# xmas-snow_sob.net
KiCad netlist of a schematic drawn in EAGLE
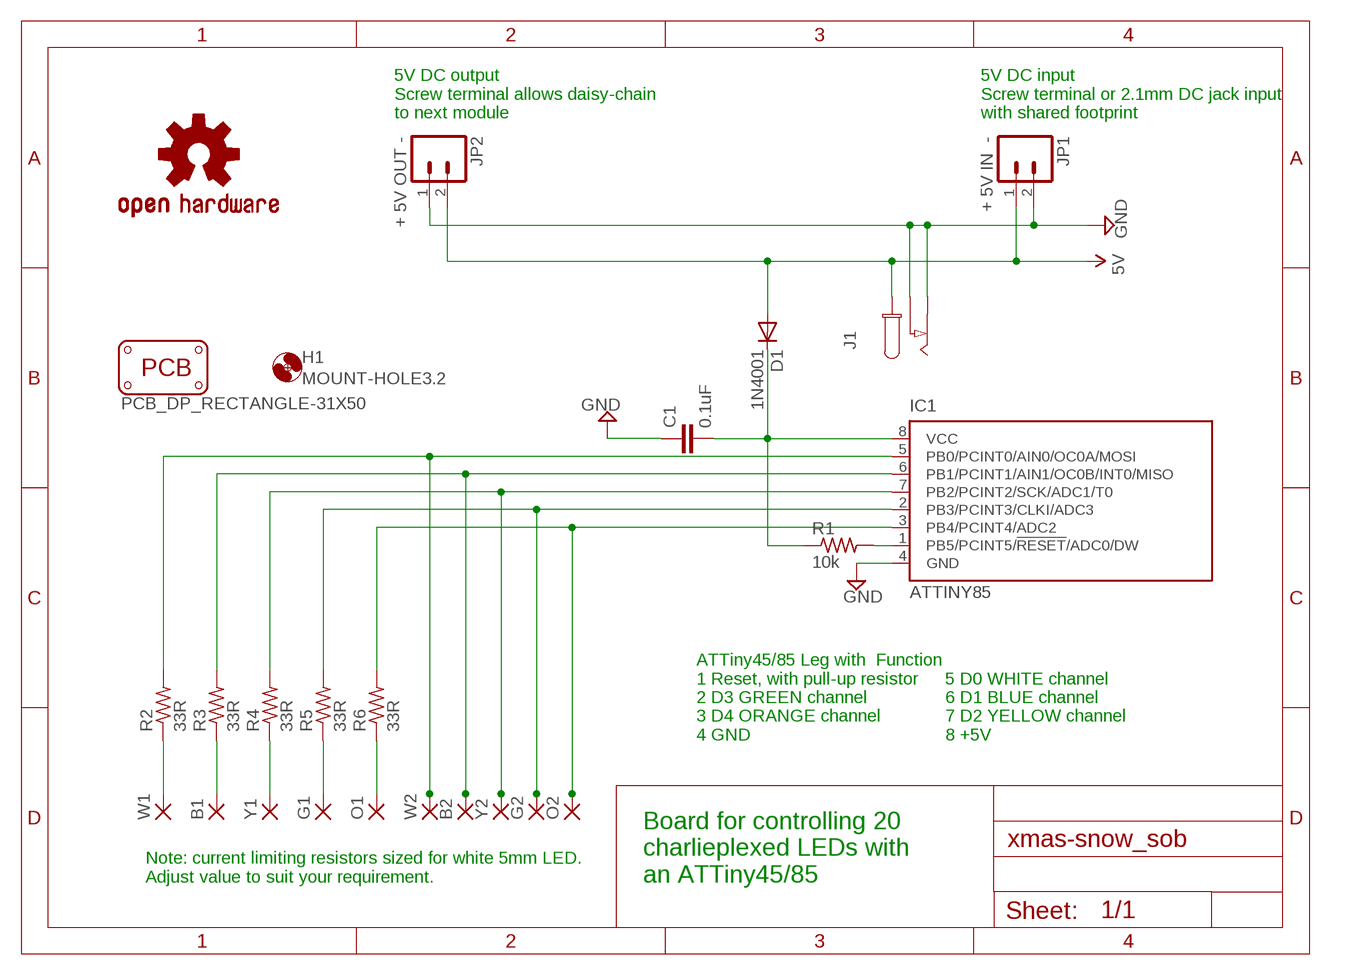
[diagram p0: schematic, sheet 1]

(export (version "E")
  (design (tool "Eeschema 10.0.6"))
  (components
    (comp (ref "B1")
      (value "WIREPAD1,6/0,8")
      (footprint "eagle-import:1,6_0,8")
      (libsource (lib "eagle-import") (part "WIREPAD1,6/0,8"))
    )
    (comp (ref "B2")
      (value "WIREPAD1,6/0,8")
      (footprint "eagle-import:1,6_0,8")
      (libsource (lib "eagle-import") (part "WIREPAD1,6/0,8"))
    )
    (comp (ref "C1")
      (value "0.1uF")
      (footprint "eagle-import:CAP-PTH-SMALL2")
      (libsource (lib "eagle-import") (part "CAPPTH2"))
    )
    (comp (ref "D1")
      (value "1N4001")
      (footprint "eagle-import:DO41-10")
      (libsource (lib "eagle-import") (part "1N4004"))
    )
    (comp (ref "G1")
      (value "WIREPAD1,6/0,8")
      (footprint "eagle-import:1,6_0,8")
      (libsource (lib "eagle-import") (part "WIREPAD1,6/0,8"))
    )
    (comp (ref "G2")
      (value "WIREPAD1,6/0,8")
      (footprint "eagle-import:1,6_0,8")
      (libsource (lib "eagle-import") (part "WIREPAD1,6/0,8"))
    )
    (comp (ref "H1")
      (value "MOUNT-HOLE3.2")
      (footprint "eagle-import:3,2")
      (libsource (lib "eagle-import") (part "MOUNT-HOLE3.2"))
    )
    (comp (ref "IC1")
      (value "ATTINY85")
      (footprint "eagle-import:DIL08")
      (fields (field (name "MPN") "ATTINY13-20PU"))
      (libsource (lib "eagle-import") (part "TINY13PU-20"))
    )
    (comp (ref "J1")
      (value "CON_DC_M-DC_PTH")
      (footprint "eagle-import:DC_BARREL_JACK_PTH_2MM")
      (libsource (lib "eagle-import") (part "CON_DC_M-DC_PTH"))
    )
    (comp (ref "JP1")
      (value "+ 5V IN -")
      (footprint "eagle-import:SCREWTERMINAL-5MM-2")
      (libsource (lib "eagle-import") (part "M025MM"))
    )
    (comp (ref "JP2")
      (value "+ 5V OUT -")
      (footprint "eagle-import:SCREWTERMINAL-5MM-2")
      (libsource (lib "eagle-import") (part "M025MM"))
    )
    (comp (ref "LOGO1")
      (value "OSHW-LOGOL")
      (footprint "eagle-import:OSHW-LOGO-L")
      (libsource (lib "eagle-import") (part "OSHW-LOGOL"))
    )
    (comp (ref "O1")
      (value "WIREPAD1,6/0,8")
      (footprint "eagle-import:1,6_0,8")
      (libsource (lib "eagle-import") (part "WIREPAD1,6/0,8"))
    )
    (comp (ref "O2")
      (value "WIREPAD1,6/0,8")
      (footprint "eagle-import:1,6_0,8")
      (libsource (lib "eagle-import") (part "WIREPAD1,6/0,8"))
    )
    (comp (ref "PCB1")
      (value "PCB_DP_RECTANGLE-31X50")
      (footprint "eagle-import:DP5031_V1")
      (libsource (lib "eagle-import") (part "PCB_DP_RECTANGLE-31X50"))
    )
    (comp (ref "R1")
      (value "10k")
      (footprint "eagle-import:0207_2V")
      (libsource (lib "eagle-import") (part "R-US_0207/2V"))
    )
    (comp (ref "R2")
      (value "33R")
      (footprint "eagle-import:0207_2V")
      (libsource (lib "eagle-import") (part "R-US_0207/2V"))
    )
    (comp (ref "R3")
      (value "33R")
      (footprint "eagle-import:0207_2V")
      (libsource (lib "eagle-import") (part "R-US_0207/2V"))
    )
    (comp (ref "R4")
      (value "33R")
      (footprint "eagle-import:0207_2V")
      (libsource (lib "eagle-import") (part "R-US_0207/2V"))
    )
    (comp (ref "R5")
      (value "33R")
      (footprint "eagle-import:0207_2V")
      (libsource (lib "eagle-import") (part "R-US_0207/2V"))
    )
    (comp (ref "R6")
      (value "33R")
      (footprint "eagle-import:0207_2V")
      (libsource (lib "eagle-import") (part "R-US_0207/2V"))
    )
    (comp (ref "W1")
      (value "WIREPAD1,6/0,8")
      (footprint "eagle-import:1,6_0,8")
      (libsource (lib "eagle-import") (part "WIREPAD1,6/0,8"))
    )
    (comp (ref "W2")
      (value "WIREPAD1,6/0,8")
      (footprint "eagle-import:1,6_0,8")
      (libsource (lib "eagle-import") (part "WIREPAD1,6/0,8"))
    )
    (comp (ref "Y1")
      (value "WIREPAD1,6/0,8")
      (footprint "eagle-import:1,6_0,8")
      (libsource (lib "eagle-import") (part "WIREPAD1,6/0,8"))
    )
    (comp (ref "Y2")
      (value "WIREPAD1,6/0,8")
      (footprint "eagle-import:1,6_0,8")
      (libsource (lib "eagle-import") (part "WIREPAD1,6/0,8"))
    )
  )
  (nets
    (net (code "1") (name "5V") (class "Default")
      (node (ref "C1") (pin "2") (pinfunction "2_2") (pintype "passive"))
      (node (ref "D1") (pin "A") (pinfunction "A_A") (pintype "passive"))
      (node (ref "D1") (pin "C") (pinfunction "C_C") (pintype "passive"))
      (node (ref "IC1") (pin "8") (pinfunction "VCC_8") (pintype "power_in"))
      (node (ref "J1") (pin "P1") (pinfunction "P1_P1") (pintype "passive"))
      (node (ref "JP1") (pin "1") (pinfunction "1_1") (pintype "passive"))
      (node (ref "JP2") (pin "2") (pinfunction "2_2") (pintype "passive"))
      (node (ref "R1") (pin "1") (pinfunction "1_1") (pintype "passive"))
    )
    (net (code "2") (name "GND") (class "Default")
      (node (ref "C1") (pin "1") (pinfunction "1_1") (pintype "passive"))
      (node (ref "IC1") (pin "4") (pinfunction "GND_4") (pintype "power_in"))
      (node (ref "J1") (pin "P2") (pinfunction "P3_P2") (pintype "passive"))
      (node (ref "J1") (pin "P3") (pinfunction "P2_P3") (pintype "passive"))
      (node (ref "JP1") (pin "2") (pinfunction "2_2") (pintype "passive"))
      (node (ref "JP2") (pin "1") (pinfunction "1_1") (pintype "passive"))
    )
    (net (code "3") (name "Net-(B1-P)") (class "Default")
      (node (ref "B1") (pin "1") (pinfunction "P_1") (pintype "passive"))
      (node (ref "R3") (pin "1") (pinfunction "1_1") (pintype "passive"))
    )
    (net (code "4") (name "Net-(B2-P)") (class "Default")
      (node (ref "B2") (pin "1") (pinfunction "P_1") (pintype "passive"))
      (node (ref "IC1") (pin "6") (pinfunction "PB1/PCINT1/AIN1/OC0B/INT0/MISO_6") (pintype "bidirectional"))
      (node (ref "R3") (pin "2") (pinfunction "2_2") (pintype "passive"))
    )
    (net (code "5") (name "Net-(G1-P)") (class "Default")
      (node (ref "G1") (pin "1") (pinfunction "P_1") (pintype "passive"))
      (node (ref "R5") (pin "1") (pinfunction "1_1") (pintype "passive"))
    )
    (net (code "6") (name "Net-(G2-P)") (class "Default")
      (node (ref "G2") (pin "1") (pinfunction "P_1") (pintype "passive"))
      (node (ref "IC1") (pin "2") (pinfunction "PB3/PCINT3/CLKI/ADC3_2") (pintype "bidirectional"))
      (node (ref "R5") (pin "2") (pinfunction "2_2") (pintype "passive"))
    )
    (net (code "7") (name "Net-(IC1-PB0{slash}PCINT0{slash}AIN0{slash}OC0A{slash}MOSI)") (class "Default")
      (node (ref "IC1") (pin "5") (pinfunction "PB0/PCINT0/AIN0/OC0A/MOSI_5") (pintype "bidirectional"))
      (node (ref "R2") (pin "2") (pinfunction "2_2") (pintype "passive"))
      (node (ref "W2") (pin "1") (pinfunction "P_1") (pintype "passive"))
    )
    (net (code "8") (name "Net-(IC1-PB2{slash}PCINT2{slash}SCK{slash}ADC1{slash}T0)") (class "Default")
      (node (ref "IC1") (pin "7") (pinfunction "PB2/PCINT2/SCK/ADC1/T0_7") (pintype "bidirectional"))
      (node (ref "R4") (pin "2") (pinfunction "2_2") (pintype "passive"))
      (node (ref "Y2") (pin "1") (pinfunction "P_1") (pintype "passive"))
    )
    (net (code "9") (name "Net-(IC1-PB4{slash}PCINT4{slash}ADC2)") (class "Default")
      (node (ref "IC1") (pin "3") (pinfunction "PB4/PCINT4/ADC2_3") (pintype "bidirectional"))
      (node (ref "O2") (pin "1") (pinfunction "P_1") (pintype "passive"))
      (node (ref "R6") (pin "2") (pinfunction "2_2") (pintype "passive"))
    )
    (net (code "10") (name "Net-(IC1-PB5{slash}PCINT5{slash}~{RESET}{slash}ADC0{slash}DW)") (class "Default")
      (node (ref "IC1") (pin "1") (pinfunction "PB5/PCINT5/~{RESET}/ADC0/DW_1") (pintype "bidirectional"))
      (node (ref "R1") (pin "2") (pinfunction "2_2") (pintype "passive"))
    )
    (net (code "11") (name "Net-(O1-P)") (class "Default")
      (node (ref "O1") (pin "1") (pinfunction "P_1") (pintype "passive"))
      (node (ref "R6") (pin "1") (pinfunction "1_1") (pintype "passive"))
    )
    (net (code "12") (name "Net-(W1-P)") (class "Default")
      (node (ref "R2") (pin "1") (pinfunction "1_1") (pintype "passive"))
      (node (ref "W1") (pin "1") (pinfunction "P_1") (pintype "passive"))
    )
    (net (code "13") (name "Net-(Y1-P)") (class "Default")
      (node (ref "R4") (pin "1") (pinfunction "1_1") (pintype "passive"))
      (node (ref "Y1") (pin "1") (pinfunction "P_1") (pintype "passive"))
    )
  )
)
